# conn_harness_lv.net
KiCad netlist of a schematic drawn in Altium Designer
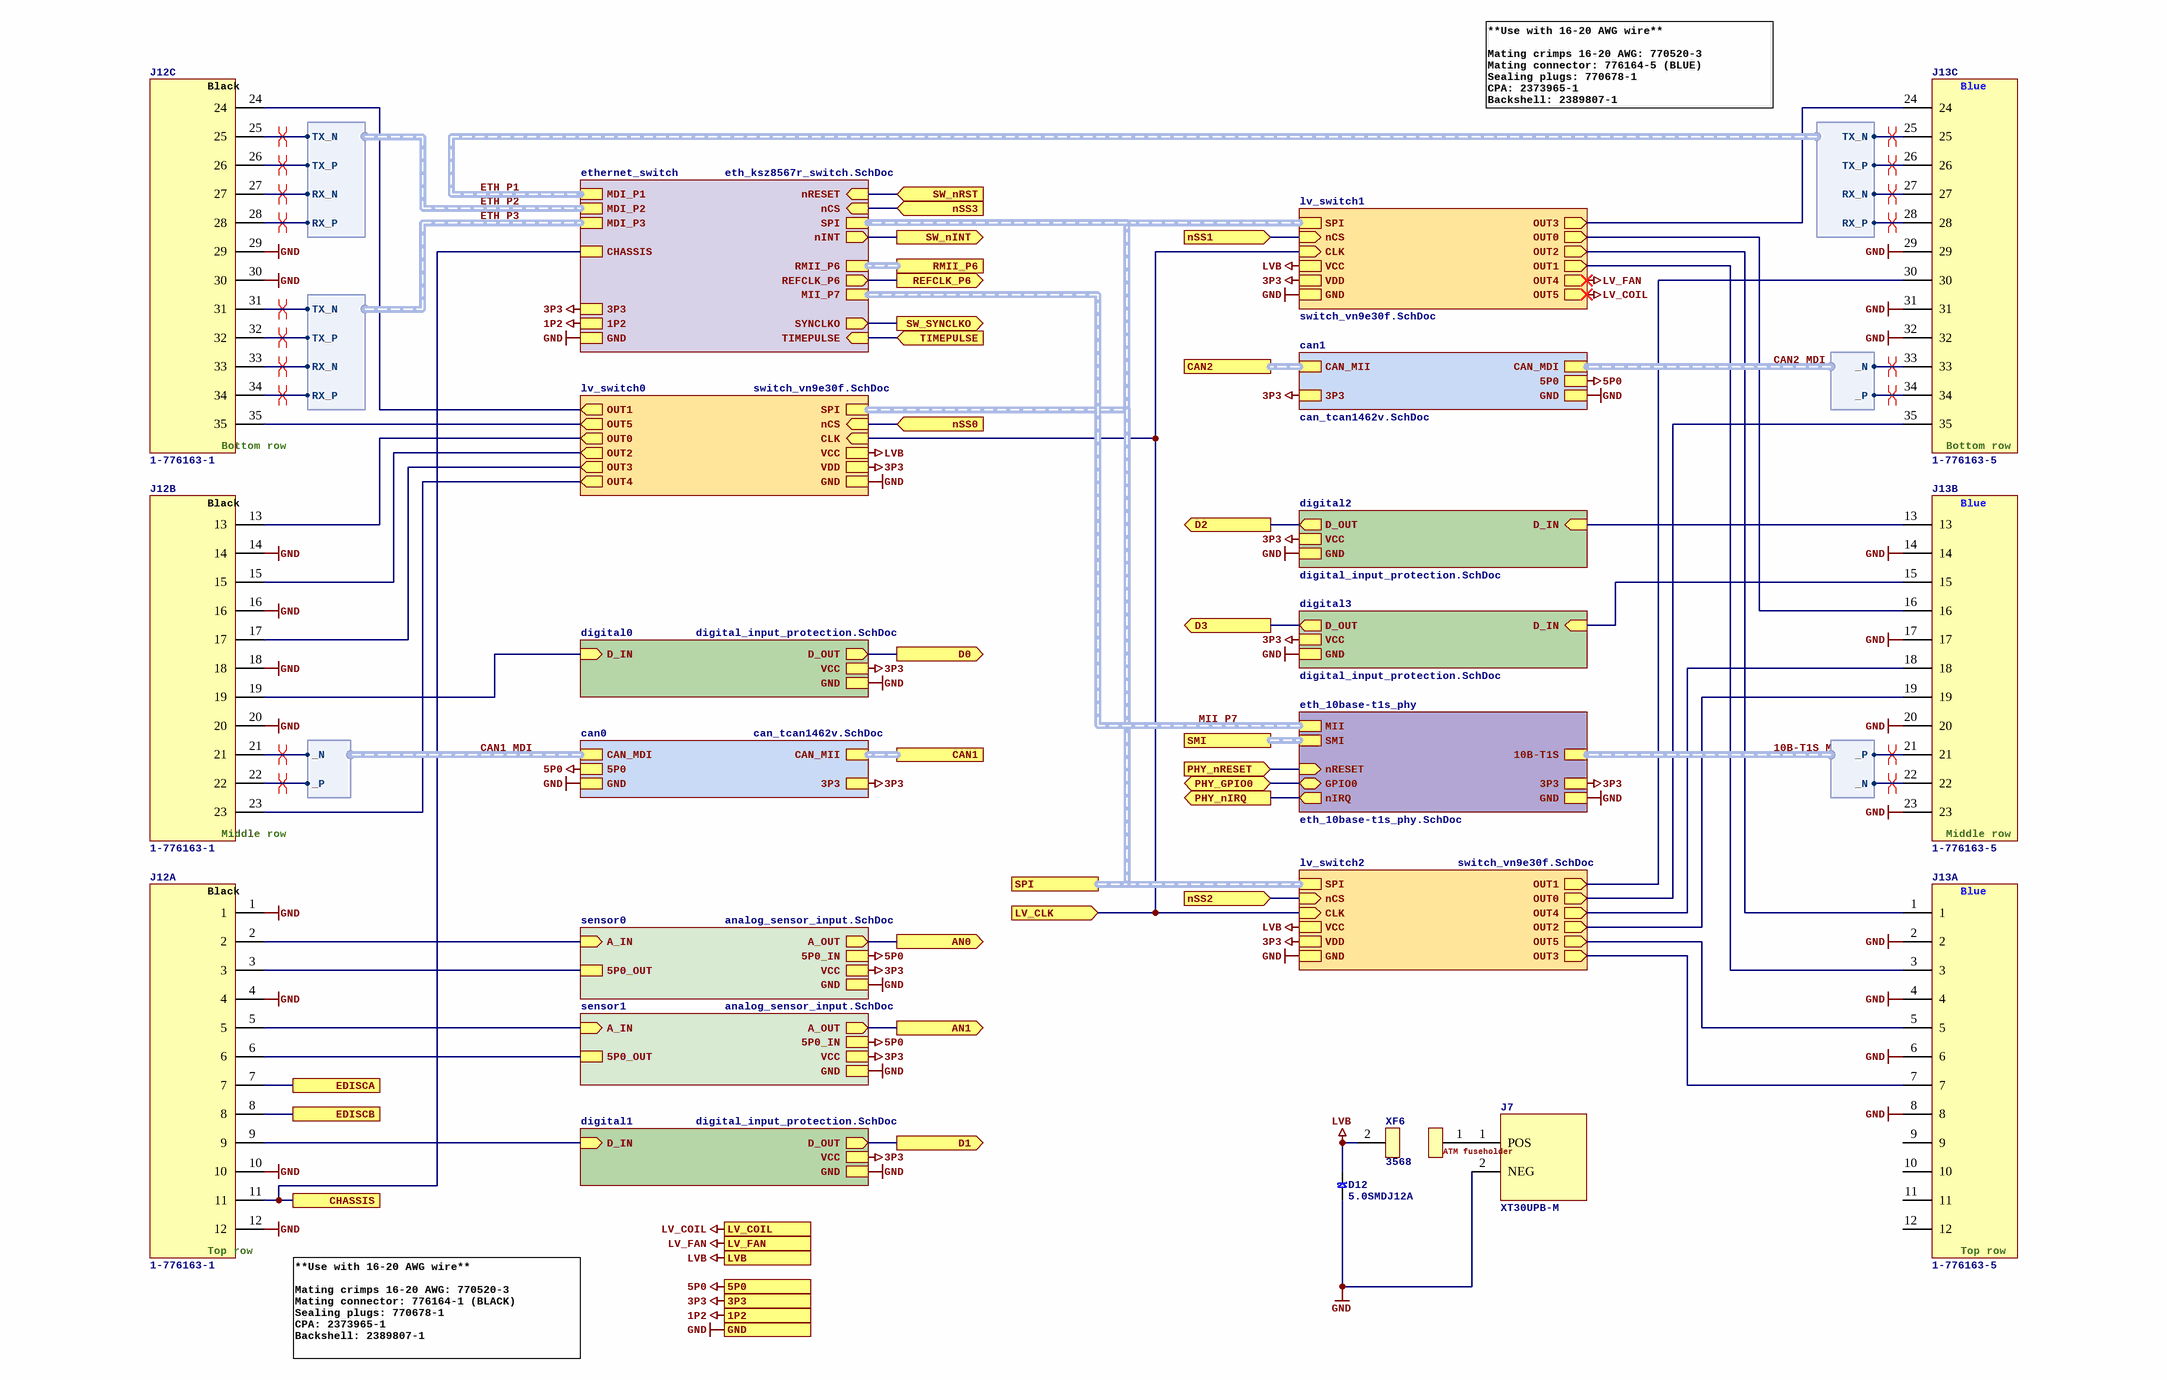
[diagram p0: conn_harness_lv.SchDoc]

(export (version "E")
  (design (tool "Eeschema 10.0.6"))
  (components
    (comp (ref "D12")
      (value "5.0SMDJ12A")
      (footprint "SMC")
      (description "TVS 5000W 12V UNIDIRECT SMCJ")
      (fields (field (name "MANUFACTURER") "Littelfuse"))
      (libsource (lib "SSCP") (part "TVS_UNI_5.0SMDJ12A"))
    )
    (comp (ref "J7")
      (value "XT30UPB-M")
      (footprint "AMASS_XT30UPB-M")
      (description "Vertical PCB mount XT30 male")
      (fields (field (name "MANUFACTURER") "Changzhou Amass Elec"))
      (libsource (lib "SSCP") (part "CONN_AMASS_2POS_VERT_XT30UPB-M"))
    )
    (comp (ref "J12")
      (value "1-776163-1")
      (footprint "TE_AMPSEAL_1-776163-1")
      (description "Conn Power PL 35 POS 4mm Solder RA Thru-Hole 35 Terminal 1 Port, BLACK")
      (fields (field (name "MANUFACTURER") "TE Connectivity"))
      (libsource (lib "SSCP") (part "CONN_AMPSEAL_35POS_RA_1-776163-1"))
    )
    (comp (ref "J13")
      (value "1-776163-5")
      (footprint "TE_AMPSEAL_1-776163-5")
      (description "Conn Power PL 35 POS 4mm Solder RA Thru-Hole 35 Terminal 1 Port, BLUE")
      (fields (field (name "MANUFACTURER") "TE Connectivity"))
      (libsource (lib "SSCP") (part "CONN_AMPSEAL_35POS_RA_1-776163-5"))
    )
    (comp (ref "XF6")
      (value "3568")
      (footprint "FUSEHOLDER_KEYSTONE_3568")
      (description "Fuse Holder 30 A 500V 1 Circuit Blade Through Hole")
      (fields (field (name "MANUFACTURER") "Keystone Electronics"))
      (libsource (lib "SSCP") (part "FUSEHOLDER_KEYSTONE_3568"))
    )
  )
  (nets
    (net (code "13") (name "/5P0_OUT") (class "Default")
      (node (ref "J12") (pin "6") (pinfunction "6_6") (pintype "passive"))
    )
    (net (code "14") (name "/5P0_OUT_1") (class "Default")
      (node (ref "J12") (pin "3") (pinfunction "3_3") (pintype "passive"))
    )
    (net (code "18") (name "/A_IN") (class "Default")
      (node (ref "J12") (pin "5") (pinfunction "5_5") (pintype "passive"))
    )
    (net (code "19") (name "/A_IN_1") (class "Default")
      (node (ref "J12") (pin "2") (pinfunction "2_2") (pintype "passive"))
    )
    (net (code "24") (name "/CHASSIS") (class "Default")
      (node (ref "J12") (pin "11") (pinfunction "11_11") (pintype "passive"))
    )
    (net (code "29") (name "/D_IN") (class "Default")
      (node (ref "J13") (pin "13") (pinfunction "13_13") (pintype "passive"))
    )
    (net (code "30") (name "/D_IN_1") (class "Default")
      (node (ref "J12") (pin "19") (pinfunction "19_19") (pintype "passive"))
    )
    (net (code "31") (name "/D_IN_2") (class "Default")
      (node (ref "J12") (pin "9") (pinfunction "9_9") (pintype "passive"))
    )
    (net (code "32") (name "/D_IN_3") (class "Default")
      (node (ref "J13") (pin "15") (pinfunction "15_15") (pintype "passive"))
    )
    (net (code "33") (name "/EDISCA") (class "Default")
      (node (ref "J12") (pin "7") (pinfunction "7_7") (pintype "passive"))
    )
    (net (code "34") (name "/EDISCB") (class "Default")
      (node (ref "J12") (pin "8") (pinfunction "8_8") (pintype "passive"))
    )
    (net (code "39") (name "/OUT0") (class "Default")
      (node (ref "J13") (pin "35") (pinfunction "35_35") (pintype "passive"))
    )
    (net (code "40") (name "/OUT0_1") (class "Default")
      (node (ref "J12") (pin "13") (pinfunction "13_13") (pintype "passive"))
    )
    (net (code "41") (name "/OUT0_2") (class "Default")
      (node (ref "J13") (pin "16") (pinfunction "16_16") (pintype "passive"))
    )
    (net (code "42") (name "/OUT1") (class "Default")
      (node (ref "J13") (pin "30") (pinfunction "30_30") (pintype "passive"))
    )
    (net (code "43") (name "/OUT1_1") (class "Default")
      (node (ref "J12") (pin "24") (pinfunction "24_24") (pintype "passive"))
    )
    (net (code "44") (name "/OUT1_2") (class "Default")
      (node (ref "J13") (pin "3") (pinfunction "3_3") (pintype "passive"))
    )
    (net (code "45") (name "/OUT2") (class "Default")
      (node (ref "J13") (pin "19") (pinfunction "19_19") (pintype "passive"))
    )
    (net (code "46") (name "/OUT2_1") (class "Default")
      (node (ref "J12") (pin "15") (pinfunction "15_15") (pintype "passive"))
    )
    (net (code "47") (name "/OUT2_2") (class "Default")
      (node (ref "J13") (pin "1") (pinfunction "1_1") (pintype "passive"))
    )
    (net (code "48") (name "/OUT3") (class "Default")
      (node (ref "J13") (pin "7") (pinfunction "7_7") (pintype "passive"))
    )
    (net (code "49") (name "/OUT3_1") (class "Default")
      (node (ref "J12") (pin "17") (pinfunction "17_17") (pintype "passive"))
    )
    (net (code "50") (name "/OUT3_2") (class "Default")
      (node (ref "J13") (pin "24") (pinfunction "24_24") (pintype "passive"))
    )
    (net (code "51") (name "/OUT4") (class "Default")
      (node (ref "J13") (pin "18") (pinfunction "18_18") (pintype "passive"))
    )
    (net (code "52") (name "/OUT4_1") (class "Default")
      (node (ref "J12") (pin "23") (pinfunction "23_23") (pintype "passive"))
    )
    (net (code "53") (name "/OUT5") (class "Default")
      (node (ref "J13") (pin "5") (pinfunction "5_5") (pintype "passive"))
    )
    (net (code "54") (name "/OUT5_1") (class "Default")
      (node (ref "J12") (pin "35") (pinfunction "35_35") (pintype "passive"))
    )
    (net (code "74") (name "GND") (class "Default")
      (node (ref "D12") (pin "1") (pintype "passive"))
      (node (ref "J12") (pin "1") (pinfunction "1_1") (pintype "passive"))
      (node (ref "J12") (pin "10") (pinfunction "10_10") (pintype "passive"))
      (node (ref "J12") (pin "12") (pinfunction "12_12") (pintype "passive"))
      (node (ref "J12") (pin "14") (pinfunction "14_14") (pintype "passive"))
      (node (ref "J12") (pin "16") (pinfunction "16_16") (pintype "passive"))
      (node (ref "J12") (pin "18") (pinfunction "18_18") (pintype "passive"))
      (node (ref "J12") (pin "20") (pinfunction "20_20") (pintype "passive"))
      (node (ref "J12") (pin "29") (pinfunction "29_29") (pintype "passive"))
      (node (ref "J12") (pin "30") (pinfunction "30_30") (pintype "passive"))
      (node (ref "J12") (pin "4") (pinfunction "4_4") (pintype "passive"))
      (node (ref "J13") (pin "14") (pinfunction "14_14") (pintype "passive"))
      (node (ref "J13") (pin "17") (pinfunction "17_17") (pintype "passive"))
      (node (ref "J13") (pin "2") (pinfunction "2_2") (pintype "passive"))
      (node (ref "J13") (pin "20") (pinfunction "20_20") (pintype "passive"))
      (node (ref "J13") (pin "23") (pinfunction "23_23") (pintype "passive"))
      (node (ref "J13") (pin "29") (pinfunction "29_29") (pintype "passive"))
      (node (ref "J13") (pin "31") (pinfunction "31_31") (pintype "passive"))
      (node (ref "J13") (pin "32") (pinfunction "32_32") (pintype "passive"))
      (node (ref "J13") (pin "4") (pinfunction "4_4") (pintype "passive"))
      (node (ref "J13") (pin "6") (pinfunction "6_6") (pintype "passive"))
      (node (ref "J13") (pin "8") (pinfunction "8_8") (pintype "passive"))
      (node (ref "J7") (pin "2") (pinfunction "NEG_2") (pintype "passive"))
    )
    (net (code "75") (name "LVB") (class "Default")
      (node (ref "D12") (pin "2") (pintype "passive"))
      (node (ref "XF6") (pin "2") (pintype "passive"))
    )
    (net (code "78") (name "Net-(J7-POS)") (class "Default")
      (node (ref "J7") (pin "1") (pinfunction "POS_1") (pintype "passive"))
      (node (ref "XF6") (pin "1") (pintype "passive"))
    )
    (net (code "79") (name "unconnected-(J12-Pad21)") (class "Default")
      (node (ref "J12") (pin "21") (pinfunction "21_21") (pintype "passive"))
    )
    (net (code "80") (name "unconnected-(J12-Pad22)") (class "Default")
      (node (ref "J12") (pin "22") (pinfunction "22_22") (pintype "passive"))
    )
    (net (code "81") (name "unconnected-(J12-Pad25)") (class "Default")
      (node (ref "J12") (pin "25") (pinfunction "25_25") (pintype "passive"))
    )
    (net (code "82") (name "unconnected-(J12-Pad26)") (class "Default")
      (node (ref "J12") (pin "26") (pinfunction "26_26") (pintype "passive"))
    )
    (net (code "83") (name "unconnected-(J12-Pad27)") (class "Default")
      (node (ref "J12") (pin "27") (pinfunction "27_27") (pintype "passive"))
    )
    (net (code "84") (name "unconnected-(J12-Pad28)") (class "Default")
      (node (ref "J12") (pin "28") (pinfunction "28_28") (pintype "passive"))
    )
    (net (code "85") (name "unconnected-(J12-Pad31)") (class "Default")
      (node (ref "J12") (pin "31") (pinfunction "31_31") (pintype "passive"))
    )
    (net (code "86") (name "unconnected-(J12-Pad32)") (class "Default")
      (node (ref "J12") (pin "32") (pinfunction "32_32") (pintype "passive"))
    )
    (net (code "87") (name "unconnected-(J12-Pad33)") (class "Default")
      (node (ref "J12") (pin "33") (pinfunction "33_33") (pintype "passive"))
    )
    (net (code "88") (name "unconnected-(J12-Pad34)") (class "Default")
      (node (ref "J12") (pin "34") (pinfunction "34_34") (pintype "passive"))
    )
    (net (code "89") (name "unconnected-(J13-Pad9)") (class "Default")
      (node (ref "J13") (pin "9") (pinfunction "9_9") (pintype "passive"))
    )
    (net (code "90") (name "unconnected-(J13-Pad10)") (class "Default")
      (node (ref "J13") (pin "10") (pinfunction "10_10") (pintype "passive"))
    )
    (net (code "91") (name "unconnected-(J13-Pad11)") (class "Default")
      (node (ref "J13") (pin "11") (pinfunction "11_11") (pintype "passive"))
    )
    (net (code "92") (name "unconnected-(J13-Pad12)") (class "Default")
      (node (ref "J13") (pin "12") (pinfunction "12_12") (pintype "passive"))
    )
    (net (code "93") (name "unconnected-(J13-Pad21)") (class "Default")
      (node (ref "J13") (pin "21") (pinfunction "21_21") (pintype "passive"))
    )
    (net (code "94") (name "unconnected-(J13-Pad22)") (class "Default")
      (node (ref "J13") (pin "22") (pinfunction "22_22") (pintype "passive"))
    )
    (net (code "95") (name "unconnected-(J13-Pad25)") (class "Default")
      (node (ref "J13") (pin "25") (pinfunction "25_25") (pintype "passive"))
    )
    (net (code "96") (name "unconnected-(J13-Pad26)") (class "Default")
      (node (ref "J13") (pin "26") (pinfunction "26_26") (pintype "passive"))
    )
    (net (code "97") (name "unconnected-(J13-Pad27)") (class "Default")
      (node (ref "J13") (pin "27") (pinfunction "27_27") (pintype "passive"))
    )
    (net (code "98") (name "unconnected-(J13-Pad28)") (class "Default")
      (node (ref "J13") (pin "28") (pinfunction "28_28") (pintype "passive"))
    )
    (net (code "99") (name "unconnected-(J13-Pad33)") (class "Default")
      (node (ref "J13") (pin "33") (pinfunction "33_33") (pintype "passive"))
    )
    (net (code "100") (name "unconnected-(J13-Pad34)") (class "Default")
      (node (ref "J13") (pin "34") (pinfunction "34_34") (pintype "passive"))
    )
  )
)
